# sch_v4_cdr.net
KiCad netlist of a schematic drawn in EAGLE
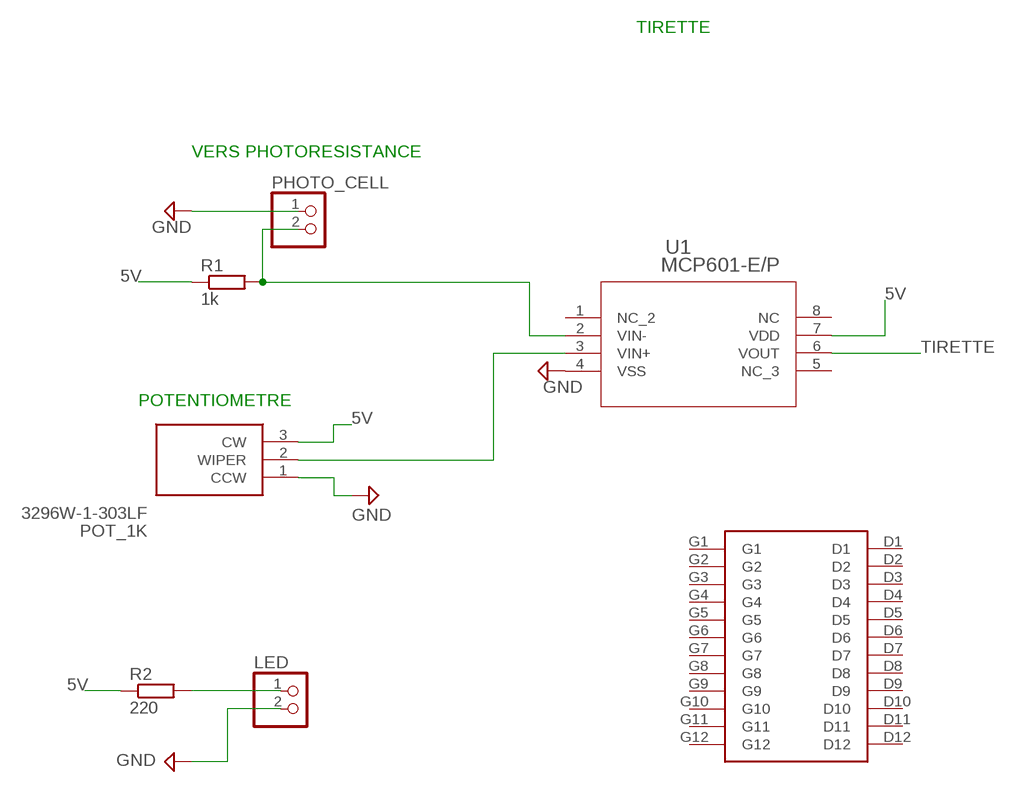
[diagram p0: schematic, sheet 1]
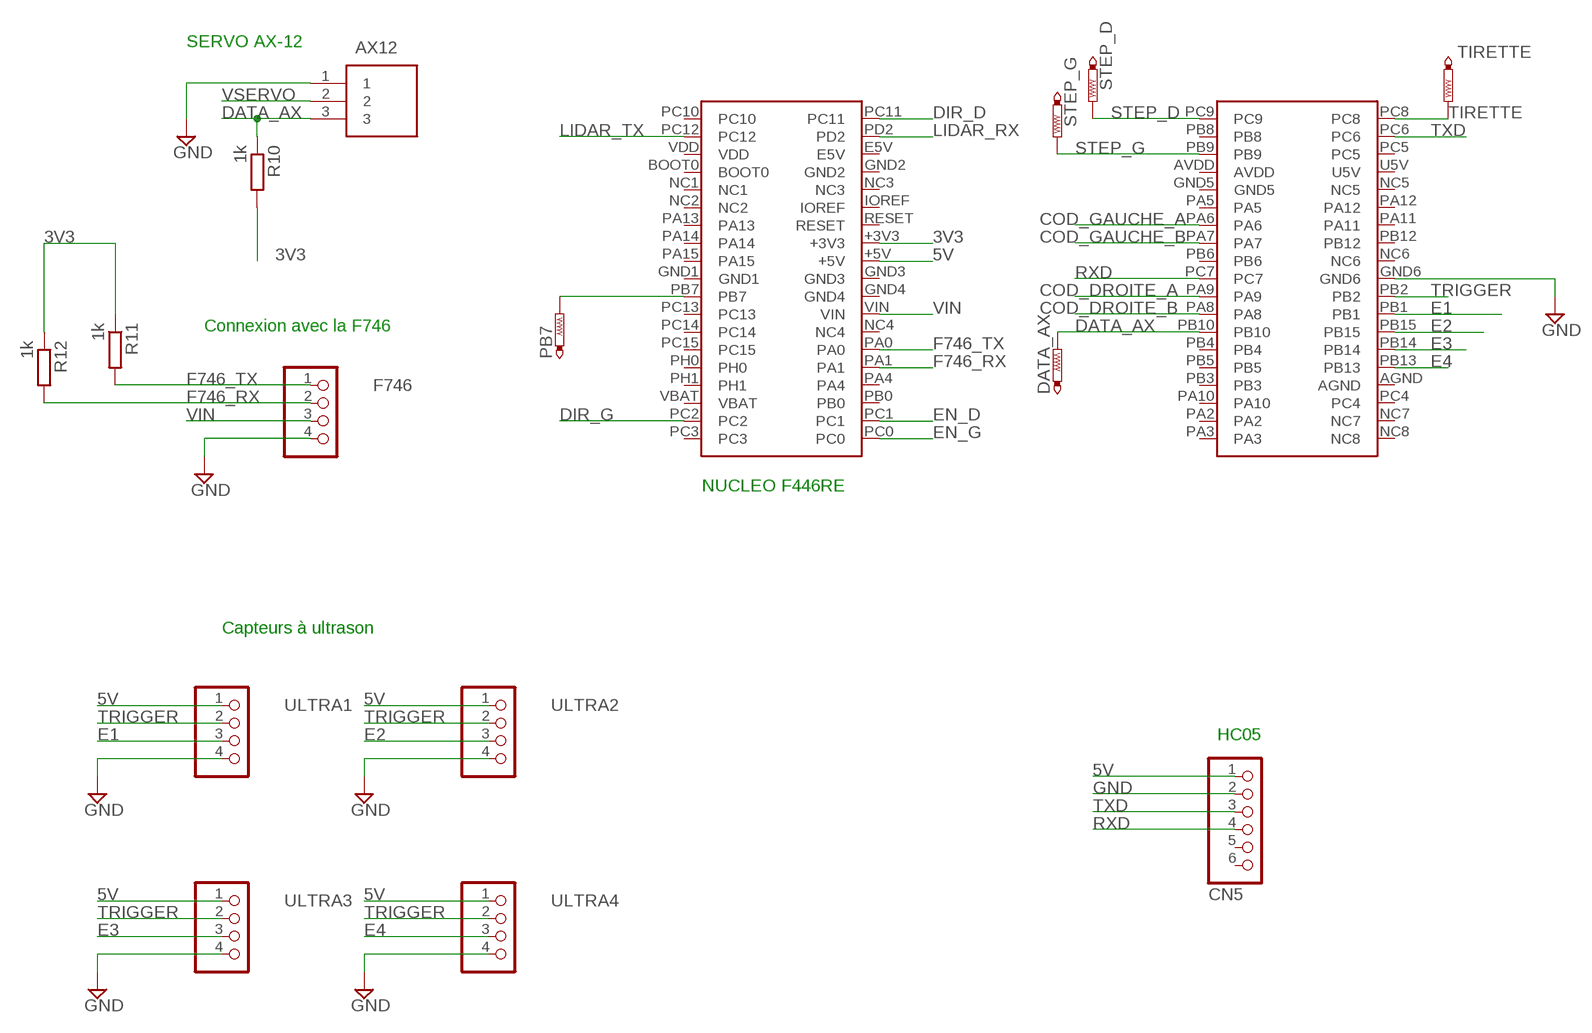
[diagram p1: schematic, sheet 2]
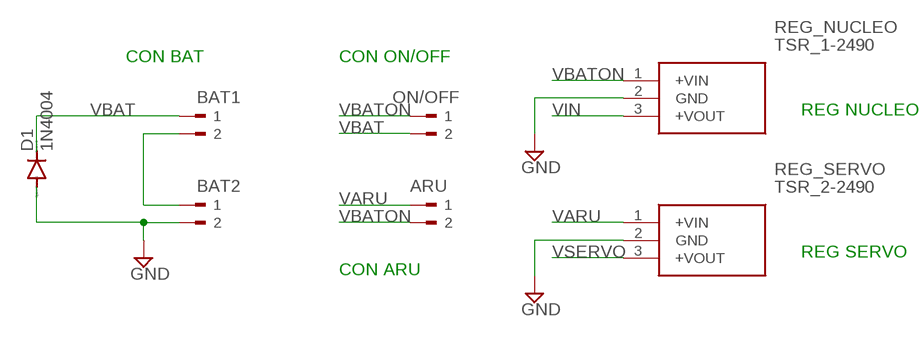
[diagram p2: schematic, sheet 3]
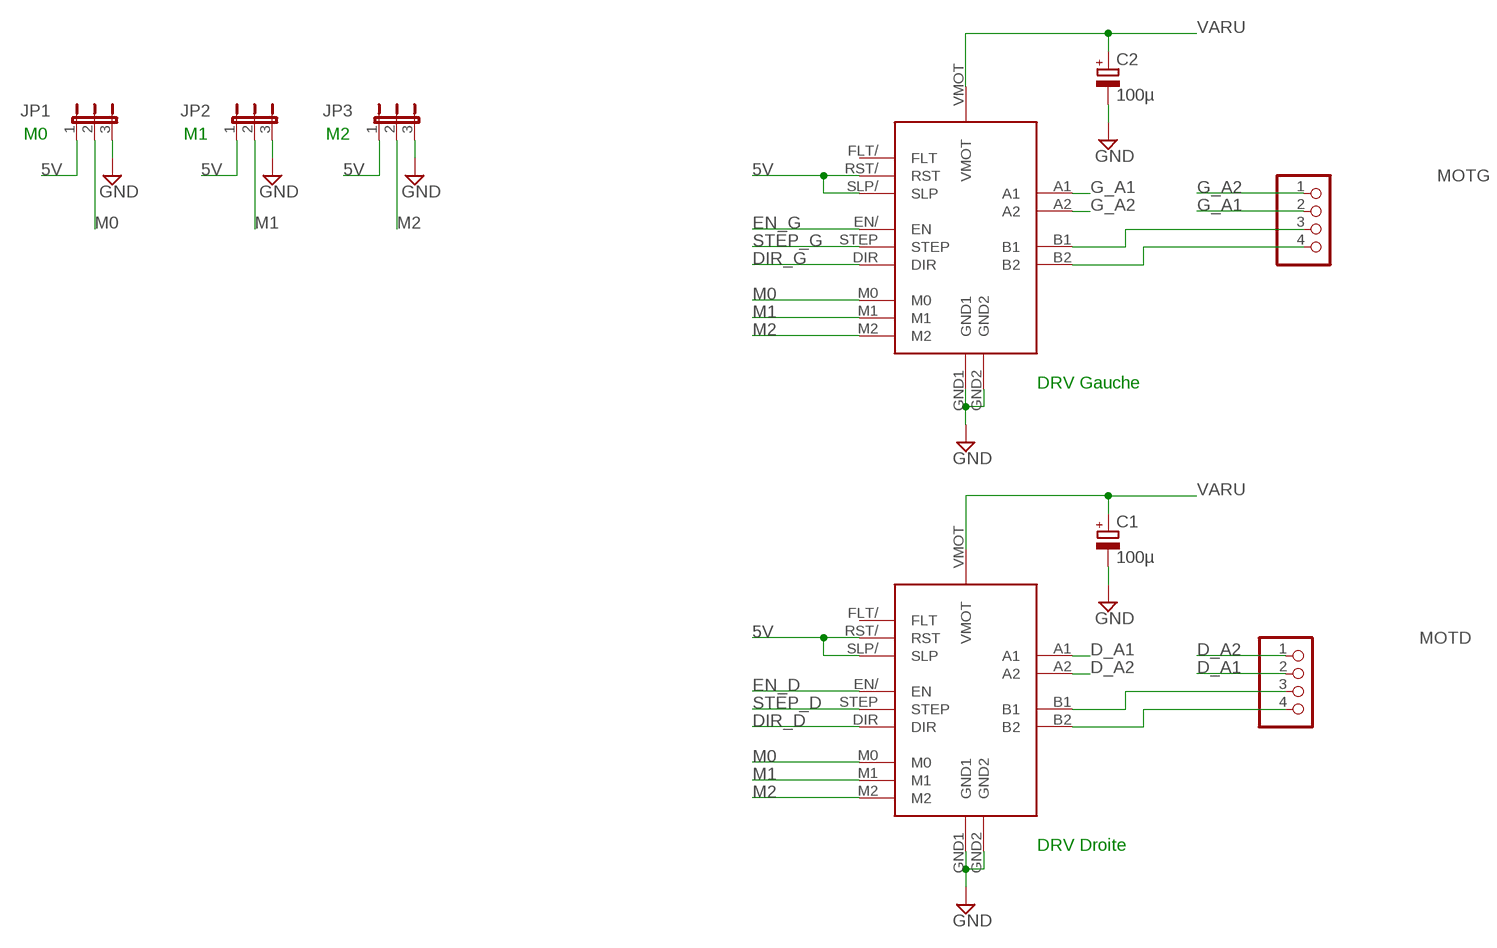
[diagram p3: schematic, sheet 4]
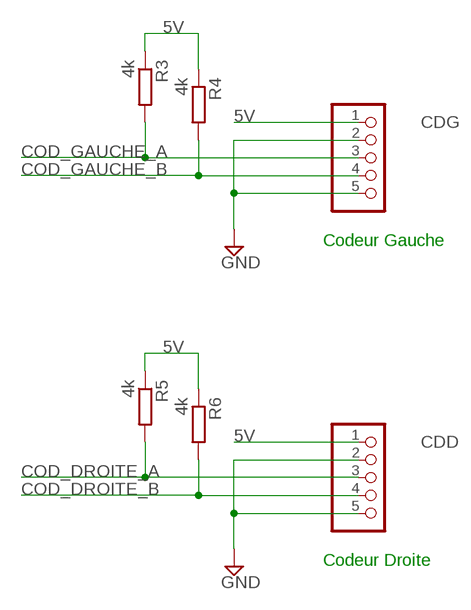
[diagram p4: schematic, sheet 5]
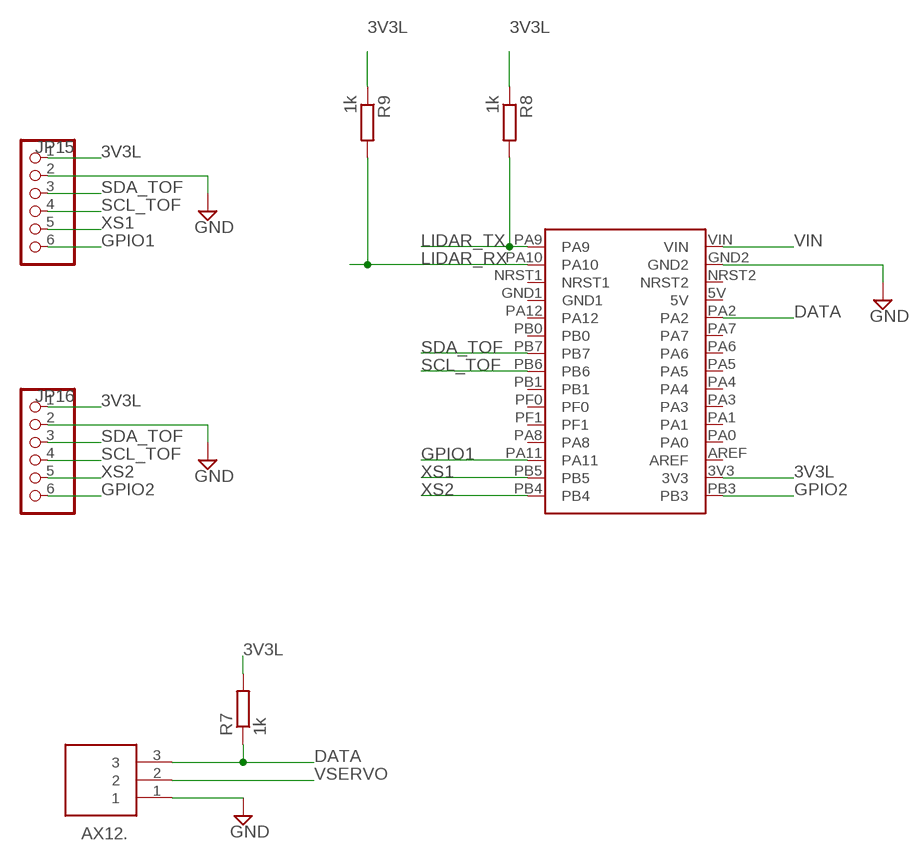
[diagram p5: schematic, sheet 6]

(export (version "E")
  (design (tool "Eeschema 10.0.6"))
  (components
    (comp (ref "AX12")
      (value "22-03-5035")
      (footprint "eagle-import:SHDR3W60P0X250_1X3_990X490X590")
      (fields (field (name "RS_PART_NUMBER") "6878048P"))
      (libsource (lib "eagle-import") (part "22-03-5035"))
    )
    (comp (ref "DATA_AX")
      (value "PTR1PAD1-13")
      (footprint "eagle-import:P1-13")
      (libsource (lib "eagle-import") (part "PTR1PAD1-13"))
    )
    (comp (ref "F746")
      (value "PINHD-1X4")
      (footprint "eagle-import:1X04")
      (libsource (lib "eagle-import") (part "PINHD-1X4"))
    )
    (comp (ref "JP4")
      (value "CN5")
      (footprint "eagle-import:1X06")
      (libsource (lib "eagle-import") (part "PINHD-1X6"))
    )
    (comp (ref "PB7")
      (value "PTR1PAD1-13")
      (footprint "eagle-import:P1-13")
      (libsource (lib "eagle-import") (part "PTR1PAD1-13"))
    )
    (comp (ref "R10")
      (value "1k")
      (footprint "eagle-import:0204_7")
      (libsource (lib "eagle-import") (part "R-EU_0204/7"))
    )
    (comp (ref "R11")
      (value "1k")
      (footprint "eagle-import:0204_7")
      (libsource (lib "eagle-import") (part "R-EU_0204/7"))
    )
    (comp (ref "R12")
      (value "1k")
      (footprint "eagle-import:0204_7")
      (libsource (lib "eagle-import") (part "R-EU_0204/7"))
    )
    (comp (ref "STEP_D")
      (value "PTR1PAD1-13")
      (footprint "eagle-import:P1-13")
      (libsource (lib "eagle-import") (part "PTR1PAD1-13"))
    )
    (comp (ref "STEP_G")
      (value "PTR1PAD1-13")
      (footprint "eagle-import:P1-13")
      (libsource (lib "eagle-import") (part "PTR1PAD1-13"))
    )
    (comp (ref "TIRETTE")
      (value "PTR1PAD1-13")
      (footprint "eagle-import:P1-13")
      (libsource (lib "eagle-import") (part "PTR1PAD1-13"))
    )
    (comp (ref "U$1")
      (value "NUCLEO_F446RE")
      (footprint "eagle-import:MB1136")
      (libsource (lib "eagle-import") (part "NUCLEO_F446RE"))
    )
    (comp (ref "ULTRA1")
      (value "PINHD-1X4")
      (footprint "eagle-import:1X04")
      (libsource (lib "eagle-import") (part "PINHD-1X4"))
    )
    (comp (ref "ULTRA2")
      (value "PINHD-1X4")
      (footprint "eagle-import:1X04")
      (libsource (lib "eagle-import") (part "PINHD-1X4"))
    )
    (comp (ref "ULTRA3")
      (value "PINHD-1X4")
      (footprint "eagle-import:1X04")
      (libsource (lib "eagle-import") (part "PINHD-1X4"))
    )
    (comp (ref "ULTRA4")
      (value "PINHD-1X4")
      (footprint "eagle-import:1X04")
      (libsource (lib "eagle-import") (part "PINHD-1X4"))
    )
    (comp (ref "CDD")
      (value "PINHD-1X5")
      (footprint "eagle-import:1X05")
      (libsource (lib "eagle-import") (part "PINHD-1X5"))
    )
    (comp (ref "CDG")
      (value "PINHD-1X5")
      (footprint "eagle-import:1X05")
      (libsource (lib "eagle-import") (part "PINHD-1X5"))
    )
    (comp (ref "R3")
      (value "4k")
      (footprint "eagle-import:0204_7")
      (libsource (lib "eagle-import") (part "R-EU_0204/7"))
    )
    (comp (ref "R4")
      (value "4k")
      (footprint "eagle-import:0204_7")
      (libsource (lib "eagle-import") (part "R-EU_0204/7"))
    )
    (comp (ref "R5")
      (value "4k")
      (footprint "eagle-import:0204_7")
      (libsource (lib "eagle-import") (part "R-EU_0204/7"))
    )
    (comp (ref "R6")
      (value "4k")
      (footprint "eagle-import:0204_7")
      (libsource (lib "eagle-import") (part "R-EU_0204/7"))
    )
    (comp (ref "C1")
      (value "100µ")
      (footprint "eagle-import:SANYO-OSCON_A")
      (libsource (lib "eagle-import") (part "CPOL-EUSANYO_A"))
    )
    (comp (ref "C2")
      (value "100µ")
      (footprint "eagle-import:SANYO-OSCON_A")
      (libsource (lib "eagle-import") (part "CPOL-EUSANYO_A"))
    )
    (comp (ref "JP1")
      (value "JP2E")
      (footprint "eagle-import:JP2")
      (libsource (lib "eagle-import") (part "JP2E"))
    )
    (comp (ref "JP2")
      (value "JP2E")
      (footprint "eagle-import:JP2")
      (libsource (lib "eagle-import") (part "JP2E"))
    )
    (comp (ref "JP3")
      (value "JP2E")
      (footprint "eagle-import:JP2")
      (libsource (lib "eagle-import") (part "JP2E"))
    )
    (comp (ref "MOTD")
      (value "PINHD-1X4")
      (footprint "eagle-import:1X04")
      (libsource (lib "eagle-import") (part "PINHD-1X4"))
    )
    (comp (ref "MOTG")
      (value "PINHD-1X4")
      (footprint "eagle-import:1X04")
      (libsource (lib "eagle-import") (part "PINHD-1X4"))
    )
    (comp (ref "U$2")
      (value "POLOLU_DRV8825")
      (footprint "eagle-import:POLOLU_DRV8825")
      (libsource (lib "eagle-import") (part "POLOLU_DRV8825"))
    )
    (comp (ref "U$3")
      (value "POLOLU_DRV8825")
      (footprint "eagle-import:POLOLU_DRV8825")
      (libsource (lib "eagle-import") (part "POLOLU_DRV8825"))
    )
    (comp (ref "ARU")
      (value "180G-2")
      (footprint "eagle-import:180G-2")
      (libsource (lib "eagle-import") (part "180G-2"))
    )
    (comp (ref "BAT1")
      (value "180G-2")
      (footprint "eagle-import:180G-2")
      (libsource (lib "eagle-import") (part "180G-2"))
    )
    (comp (ref "BAT2")
      (value "180G-2")
      (footprint "eagle-import:180G-2")
      (libsource (lib "eagle-import") (part "180G-2"))
    )
    (comp (ref "D1")
      (value "1N4004")
      (footprint "eagle-import:DO41-10")
      (libsource (lib "eagle-import") (part "1N4004"))
    )
    (comp (ref "ON/OFF")
      (value "180G-2")
      (footprint "eagle-import:180G-2")
      (libsource (lib "eagle-import") (part "180G-2"))
    )
    (comp (ref "REG_NUCLEO")
      (value "TSR_1-2490")
      (footprint "eagle-import:TSR_1-24XX")
      (libsource (lib "eagle-import") (part "TSR_1-2490"))
    )
    (comp (ref "REG_SERVO")
      (value "TSR_2-2490")
      (footprint "eagle-import:TSR_2-24XX")
      (fields
        (field (name "MANUFACTURER_PART_NUMBER") "TSR 2-2490")
        (field (name "MOUSER_PART_NUMBER") "495-TSR2-2490")
      )
      (libsource (lib "eagle-import") (part "TSR_2-2490"))
    )
    (comp (ref "LED")
      (value "PINHD-1X2")
      (footprint "eagle-import:1X02")
      (libsource (lib "eagle-import") (part "PINHD-1X2"))
    )
    (comp (ref "PHOTO_CELL")
      (value "PINHD-1X2")
      (footprint "eagle-import:1X02")
      (libsource (lib "eagle-import") (part "PINHD-1X2"))
    )
    (comp (ref "POT_1K")
      (value "3296W-1-303LF")
      (footprint "eagle-import:3296W-1")
      (fields (field (name "MOUSER_PART_NUMBER") "652-3296W-1-303LF"))
      (libsource (lib "eagle-import") (part "3296W-1-303LF"))
    )
    (comp (ref "R1")
      (value "1k")
      (footprint "eagle-import:0204_7")
      (libsource (lib "eagle-import") (part "R-EU_0204/7"))
    )
    (comp (ref "R2")
      (value "220")
      (footprint "eagle-import:0204_7")
      (libsource (lib "eagle-import") (part "R-EU_0204/7"))
    )
    (comp (ref "U$5")
      (value "MATRIX_12X12")
      (footprint "eagle-import:MATRIX_12X12")
      (libsource (lib "eagle-import") (part "MATRIX_12X12"))
    )
    (comp (ref "U1")
      (value "MCP601-E/P")
      (footprint "eagle-import:PDIP8_300MC_MCH")
      (fields (field (name "COPYRIGHT") "Copyright (C) 2018 Accelerated Designs. All rights reserved"))
      (libsource (lib "eagle-import") (part "MCP601-E/P"))
    )
    (comp (ref "AX12.")
      (value "22-03-5035")
      (footprint "eagle-import:SHDR3W60P0X250_1X3_990X490X590")
      (fields (field (name "RS_PART_NUMBER") "6878048P"))
      (libsource (lib "eagle-import") (part "22-03-5035"))
    )
    (comp (ref "JP15")
      (value "PINHD-1X6")
      (footprint "eagle-import:1X06")
      (libsource (lib "eagle-import") (part "PINHD-1X6"))
    )
    (comp (ref "JP16")
      (value "PINHD-1X6")
      (footprint "eagle-import:1X06")
      (libsource (lib "eagle-import") (part "PINHD-1X6"))
    )
    (comp (ref "R7")
      (value "1k")
      (footprint "eagle-import:0204_7")
      (libsource (lib "eagle-import") (part "R-EU_0204/7"))
    )
    (comp (ref "R8")
      (value "1k")
      (footprint "eagle-import:0204_7")
      (libsource (lib "eagle-import") (part "R-EU_0204/7"))
    )
    (comp (ref "R9")
      (value "1k")
      (footprint "eagle-import:0204_7")
      (libsource (lib "eagle-import") (part "R-EU_0204/7"))
    )
    (comp (ref "U$4")
      (value "NUCLEO_F303K8")
      (footprint "eagle-import:MB1180")
      (libsource (lib "eagle-import") (part "NUCLEO_F303K8"))
    )
  )
  (nets
    (net (code "1") (name "3V3") (class "Default")
      (node (ref "R10") (pin "2") (pinfunction "2_2") (pintype "passive"))
      (node (ref "R11") (pin "1") (pinfunction "1_1") (pintype "passive"))
      (node (ref "R12") (pin "1") (pinfunction "1_1") (pintype "passive"))
      (node (ref "U$1") (pin "+3V3") (pinfunction "+3V3_+3V3") (pintype "bidirectional"))
    )
    (net (code "2") (name "3V3L") (class "Default")
      (node (ref "JP15") (pin "1") (pinfunction "1_1") (pintype "passive"))
      (node (ref "JP16") (pin "1") (pinfunction "1_1") (pintype "passive"))
      (node (ref "R7") (pin "2") (pinfunction "2_2") (pintype "passive"))
      (node (ref "R8") (pin "1") (pinfunction "1_1") (pintype "passive"))
      (node (ref "R9") (pin "1") (pinfunction "1_1") (pintype "passive"))
      (node (ref "U$4") (pin "3V3") (pinfunction "3V3_3V3") (pintype "bidirectional"))
    )
    (net (code "3") (name "5V") (class "Default")
      (node (ref "CDD") (pin "1") (pinfunction "1_1") (pintype "passive"))
      (node (ref "CDG") (pin "1") (pinfunction "1_1") (pintype "passive"))
      (node (ref "JP1") (pin "1") (pinfunction "1_1") (pintype "passive"))
      (node (ref "JP2") (pin "1") (pinfunction "1_1") (pintype "passive"))
      (node (ref "JP3") (pin "1") (pinfunction "1_1") (pintype "passive"))
      (node (ref "JP4") (pin "1") (pinfunction "1_1") (pintype "passive"))
      (node (ref "POT_1K") (pin "3") (pinfunction "CW_3") (pintype "bidirectional"))
      (node (ref "R1") (pin "1") (pinfunction "1_1") (pintype "passive"))
      (node (ref "R2") (pin "1") (pinfunction "1_1") (pintype "passive"))
      (node (ref "R3") (pin "1") (pinfunction "1_1") (pintype "passive"))
      (node (ref "R4") (pin "1") (pinfunction "1_1") (pintype "passive"))
      (node (ref "R5") (pin "1") (pinfunction "1_1") (pintype "passive"))
      (node (ref "R6") (pin "1") (pinfunction "1_1") (pintype "passive"))
      (node (ref "U$1") (pin "+5V") (pinfunction "+5V_+5V") (pintype "bidirectional"))
      (node (ref "U$2") (pin "RST/") (pinfunction "RST_RST/") (pintype "bidirectional"))
      (node (ref "U$2") (pin "SLP/") (pinfunction "SLP_SLP/") (pintype "bidirectional"))
      (node (ref "U$3") (pin "RST/") (pinfunction "RST_RST/") (pintype "bidirectional"))
      (node (ref "U$3") (pin "SLP/") (pinfunction "SLP_SLP/") (pintype "bidirectional"))
      (node (ref "U1") (pin "7") (pinfunction "VDD_7") (pintype "passive"))
      (node (ref "ULTRA1") (pin "1") (pinfunction "1_1") (pintype "passive"))
      (node (ref "ULTRA2") (pin "1") (pinfunction "1_1") (pintype "passive"))
      (node (ref "ULTRA3") (pin "1") (pinfunction "1_1") (pintype "passive"))
      (node (ref "ULTRA4") (pin "1") (pinfunction "1_1") (pintype "passive"))
    )
    (net (code "4") (name "COD_DROITE_A") (class "Default")
      (node (ref "CDD") (pin "3") (pinfunction "3_3") (pintype "passive"))
      (node (ref "R5") (pin "2") (pinfunction "2_2") (pintype "passive"))
      (node (ref "U$1") (pin "PA9") (pinfunction "PA9_PA9") (pintype "bidirectional"))
    )
    (net (code "5") (name "COD_DROITE_B") (class "Default")
      (node (ref "CDD") (pin "4") (pinfunction "4_4") (pintype "passive"))
      (node (ref "R6") (pin "2") (pinfunction "2_2") (pintype "passive"))
      (node (ref "U$1") (pin "PA8") (pinfunction "PA8_PA8") (pintype "bidirectional"))
    )
    (net (code "6") (name "COD_GAUCHE_A") (class "Default")
      (node (ref "CDG") (pin "3") (pinfunction "3_3") (pintype "passive"))
      (node (ref "R3") (pin "2") (pinfunction "2_2") (pintype "passive"))
      (node (ref "U$1") (pin "PA6") (pinfunction "PA6_PA6") (pintype "bidirectional"))
    )
    (net (code "7") (name "COD_GAUCHE_B") (class "Default")
      (node (ref "CDG") (pin "4") (pinfunction "4_4") (pintype "passive"))
      (node (ref "R4") (pin "2") (pinfunction "2_2") (pintype "passive"))
      (node (ref "U$1") (pin "PA7") (pinfunction "PA7_PA7") (pintype "bidirectional"))
    )
    (net (code "8") (name "DATA") (class "Default")
      (node (ref "AX12.") (pin "3") (pinfunction "3_3") (pintype "bidirectional"))
      (node (ref "R7") (pin "1") (pinfunction "1_1") (pintype "passive"))
      (node (ref "U$4") (pin "PA2") (pinfunction "PA2_PA2") (pintype "bidirectional"))
    )
    (net (code "9") (name "DATA_AX") (class "Default")
      (node (ref "AX12") (pin "3") (pinfunction "3_3") (pintype "bidirectional"))
      (node (ref "DATA_AX") (pin "TP") (pinfunction "TP_TP") (pintype "input"))
      (node (ref "R10") (pin "1") (pinfunction "1_1") (pintype "passive"))
      (node (ref "U$1") (pin "PB10") (pinfunction "PB10_PB10") (pintype "bidirectional"))
    )
    (net (code "10") (name "DIR_D") (class "Default")
      (node (ref "U$1") (pin "PC11") (pinfunction "PC11_PC11") (pintype "bidirectional"))
      (node (ref "U$3") (pin "DIR") (pinfunction "DIR_DIR") (pintype "bidirectional"))
    )
    (net (code "11") (name "DIR_G") (class "Default")
      (node (ref "U$1") (pin "PC2") (pinfunction "PC2_PC2") (pintype "bidirectional"))
      (node (ref "U$2") (pin "DIR") (pinfunction "DIR_DIR") (pintype "bidirectional"))
    )
    (net (code "12") (name "D_A1") (class "Default")
      (node (ref "MOTD") (pin "2") (pinfunction "2_2") (pintype "passive"))
      (node (ref "U$3") (pin "A1") (pinfunction "A1_A1") (pintype "bidirectional"))
    )
    (net (code "13") (name "D_A2") (class "Default")
      (node (ref "MOTD") (pin "1") (pinfunction "1_1") (pintype "passive"))
      (node (ref "U$3") (pin "A2") (pinfunction "A2_A2") (pintype "bidirectional"))
    )
    (net (code "14") (name "E1") (class "Default")
      (node (ref "U$1") (pin "PB1") (pinfunction "PB1_PB1") (pintype "bidirectional"))
      (node (ref "ULTRA1") (pin "3") (pinfunction "3_3") (pintype "passive"))
    )
    (net (code "15") (name "E2") (class "Default")
      (node (ref "U$1") (pin "PB15") (pinfunction "PB15_PB15") (pintype "bidirectional"))
      (node (ref "ULTRA2") (pin "3") (pinfunction "3_3") (pintype "passive"))
    )
    (net (code "16") (name "E3") (class "Default")
      (node (ref "U$1") (pin "PB14") (pinfunction "PB14_PB14") (pintype "bidirectional"))
      (node (ref "ULTRA3") (pin "3") (pinfunction "3_3") (pintype "passive"))
    )
    (net (code "17") (name "E4") (class "Default")
      (node (ref "U$1") (pin "PB13") (pinfunction "PB13_PB13") (pintype "bidirectional"))
      (node (ref "ULTRA4") (pin "3") (pinfunction "3_3") (pintype "passive"))
    )
    (net (code "18") (name "EN_D") (class "Default")
      (node (ref "U$1") (pin "PC1") (pinfunction "PC1_PC1") (pintype "bidirectional"))
      (node (ref "U$3") (pin "EN/") (pinfunction "EN_EN/") (pintype "bidirectional"))
    )
    (net (code "19") (name "EN_G") (class "Default")
      (node (ref "U$1") (pin "PC0") (pinfunction "PC0_PC0") (pintype "bidirectional"))
      (node (ref "U$2") (pin "EN/") (pinfunction "EN_EN/") (pintype "bidirectional"))
    )
    (net (code "20") (name "F746_RX") (class "Default")
      (node (ref "F746") (pin "2") (pinfunction "2_2") (pintype "passive"))
      (node (ref "R12") (pin "2") (pinfunction "2_2") (pintype "passive"))
      (node (ref "U$1") (pin "PA1") (pinfunction "PA1_PA1") (pintype "bidirectional"))
    )
    (net (code "21") (name "F746_TX") (class "Default")
      (node (ref "F746") (pin "1") (pinfunction "1_1") (pintype "passive"))
      (node (ref "R11") (pin "2") (pinfunction "2_2") (pintype "passive"))
      (node (ref "U$1") (pin "PA0") (pinfunction "PA0_PA0") (pintype "bidirectional"))
    )
    (net (code "22") (name "GND") (class "Default")
      (node (ref "AX12") (pin "1") (pinfunction "1_1") (pintype "bidirectional"))
      (node (ref "AX12.") (pin "1") (pinfunction "1_1") (pintype "bidirectional"))
      (node (ref "BAT2") (pin "2") (pinfunction "2_2") (pintype "passive"))
      (node (ref "C1") (pin "-") (pinfunction "-_-") (pintype "passive"))
      (node (ref "C2") (pin "-") (pinfunction "-_-") (pintype "passive"))
      (node (ref "CDD") (pin "2") (pinfunction "2_2") (pintype "passive"))
      (node (ref "CDD") (pin "5") (pinfunction "5_5") (pintype "passive"))
      (node (ref "CDG") (pin "2") (pinfunction "2_2") (pintype "passive"))
      (node (ref "CDG") (pin "5") (pinfunction "5_5") (pintype "passive"))
      (node (ref "D1") (pin "A") (pinfunction "A_A") (pintype "passive"))
      (node (ref "F746") (pin "4") (pinfunction "4_4") (pintype "passive"))
      (node (ref "JP1") (pin "3") (pinfunction "3_3") (pintype "passive"))
      (node (ref "JP15") (pin "2") (pinfunction "2_2") (pintype "passive"))
      (node (ref "JP16") (pin "2") (pinfunction "2_2") (pintype "passive"))
      (node (ref "JP2") (pin "3") (pinfunction "3_3") (pintype "passive"))
      (node (ref "JP3") (pin "3") (pinfunction "3_3") (pintype "passive"))
      (node (ref "JP4") (pin "2") (pinfunction "2_2") (pintype "passive"))
      (node (ref "LED") (pin "2") (pinfunction "2_2") (pintype "passive"))
      (node (ref "PHOTO_CELL") (pin "1") (pinfunction "1_1") (pintype "passive"))
      (node (ref "POT_1K") (pin "1") (pinfunction "CCW_1") (pintype "bidirectional"))
      (node (ref "REG_NUCLEO") (pin "2") (pinfunction "GND_2") (pintype "bidirectional"))
      (node (ref "REG_SERVO") (pin "2") (pinfunction "GND_2") (pintype "bidirectional"))
      (node (ref "U$1") (pin "GND6") (pinfunction "GND6_GND6") (pintype "bidirectional"))
      (node (ref "U$2") (pin "GND1") (pinfunction "GND1_GND1") (pintype "bidirectional"))
      (node (ref "U$2") (pin "GND2") (pinfunction "GND2_GND2") (pintype "bidirectional"))
      (node (ref "U$3") (pin "GND1") (pinfunction "GND1_GND1") (pintype "bidirectional"))
      (node (ref "U$3") (pin "GND2") (pinfunction "GND2_GND2") (pintype "bidirectional"))
      (node (ref "U$4") (pin "GND2") (pinfunction "GND2_GND2") (pintype "bidirectional"))
      (node (ref "U1") (pin "4") (pinfunction "VSS_4") (pintype "passive"))
      (node (ref "ULTRA1") (pin "4") (pinfunction "4_4") (pintype "passive"))
      (node (ref "ULTRA2") (pin "4") (pinfunction "4_4") (pintype "passive"))
      (node (ref "ULTRA3") (pin "4") (pinfunction "4_4") (pintype "passive"))
      (node (ref "ULTRA4") (pin "4") (pinfunction "4_4") (pintype "passive"))
    )
    (net (code "23") (name "GPIO1") (class "Default")
      (node (ref "JP15") (pin "6") (pinfunction "6_6") (pintype "passive"))
      (node (ref "U$4") (pin "PA11") (pinfunction "PA11_PA11") (pintype "bidirectional"))
    )
    (net (code "24") (name "GPIO2") (class "Default")
      (node (ref "JP16") (pin "6") (pinfunction "6_6") (pintype "passive"))
      (node (ref "U$4") (pin "PB3") (pinfunction "PB3_PB3") (pintype "bidirectional"))
    )
    (net (code "25") (name "G_A1") (class "Default")
      (node (ref "MOTG") (pin "2") (pinfunction "2_2") (pintype "passive"))
      (node (ref "U$2") (pin "A1") (pinfunction "A1_A1") (pintype "bidirectional"))
    )
    (net (code "26") (name "G_A2") (class "Default")
      (node (ref "MOTG") (pin "1") (pinfunction "1_1") (pintype "passive"))
      (node (ref "U$2") (pin "A2") (pinfunction "A2_A2") (pintype "bidirectional"))
    )
    (net (code "27") (name "LIDAR_RX") (class "Default")
      (node (ref "R9") (pin "2") (pinfunction "2_2") (pintype "passive"))
      (node (ref "U$1") (pin "PD2") (pinfunction "PD2_PD2") (pintype "bidirectional"))
      (node (ref "U$4") (pin "PA10") (pinfunction "PA10_PA10") (pintype "bidirectional"))
    )
    (net (code "28") (name "LIDAR_TX") (class "Default")
      (node (ref "R8") (pin "2") (pinfunction "2_2") (pintype "passive"))
      (node (ref "U$1") (pin "PC12") (pinfunction "PC12_PC12") (pintype "bidirectional"))
      (node (ref "U$4") (pin "PA9") (pinfunction "PA9_PA9") (pintype "bidirectional"))
    )
    (net (code "29") (name "M0") (class "Default")
      (node (ref "JP1") (pin "2") (pinfunction "2_2") (pintype "passive"))
      (node (ref "U$2") (pin "M0") (pinfunction "M0_M0") (pintype "bidirectional"))
      (node (ref "U$3") (pin "M0") (pinfunction "M0_M0") (pintype "bidirectional"))
    )
    (net (code "30") (name "M1") (class "Default")
      (node (ref "JP2") (pin "2") (pinfunction "2_2") (pintype "passive"))
      (node (ref "U$2") (pin "M1") (pinfunction "M1_M1") (pintype "bidirectional"))
      (node (ref "U$3") (pin "M1") (pinfunction "M1_M1") (pintype "bidirectional"))
    )
    (net (code "31") (name "M2") (class "Default")
      (node (ref "JP3") (pin "2") (pinfunction "2_2") (pintype "passive"))
      (node (ref "U$2") (pin "M2") (pinfunction "M2_M2") (pintype "bidirectional"))
      (node (ref "U$3") (pin "M2") (pinfunction "M2_M2") (pintype "bidirectional"))
    )
    (net (code "32") (name "Net-(BAT1-Pad2)") (class "Default")
      (node (ref "BAT1") (pin "2") (pinfunction "2_2") (pintype "passive"))
      (node (ref "BAT2") (pin "1") (pinfunction "1_1") (pintype "passive"))
    )
    (net (code "33") (name "Net-(LED-Pad1)") (class "Default")
      (node (ref "LED") (pin "1") (pinfunction "1_1") (pintype "passive"))
      (node (ref "R2") (pin "2") (pinfunction "2_2") (pintype "passive"))
    )
    (net (code "34") (name "Net-(MOTD-Pad3)") (class "Default")
      (node (ref "MOTD") (pin "3") (pinfunction "3_3") (pintype "passive"))
      (node (ref "U$3") (pin "B1") (pinfunction "B1_B1") (pintype "bidirectional"))
    )
    (net (code "35") (name "Net-(MOTD-Pad4)") (class "Default")
      (node (ref "MOTD") (pin "4") (pinfunction "4_4") (pintype "passive"))
      (node (ref "U$3") (pin "B2") (pinfunction "B2_B2") (pintype "bidirectional"))
    )
    (net (code "36") (name "Net-(MOTG-Pad3)") (class "Default")
      (node (ref "MOTG") (pin "3") (pinfunction "3_3") (pintype "passive"))
      (node (ref "U$2") (pin "B1") (pinfunction "B1_B1") (pintype "bidirectional"))
    )
    (net (code "37") (name "Net-(MOTG-Pad4)") (class "Default")
      (node (ref "MOTG") (pin "4") (pinfunction "4_4") (pintype "passive"))
      (node (ref "U$2") (pin "B2") (pinfunction "B2_B2") (pintype "bidirectional"))
    )
    (net (code "38") (name "Net-(PB7-PadTP)") (class "Default")
      (node (ref "PB7") (pin "TP") (pinfunction "TP_TP") (pintype "input"))
      (node (ref "U$1") (pin "PB7") (pinfunction "PB7_PB7") (pintype "bidirectional"))
    )
    (net (code "39") (name "Net-(POT_1K-WIPER)") (class "Default")
      (node (ref "POT_1K") (pin "2") (pinfunction "WIPER_2") (pintype "bidirectional"))
      (node (ref "U1") (pin "3") (pinfunction "VIN+_3") (pintype "passive"))
    )
    (net (code "40") (name "Net-(U1-VIN-)") (class "Default")
      (node (ref "PHOTO_CELL") (pin "2") (pinfunction "2_2") (pintype "passive"))
      (node (ref "R1") (pin "2") (pinfunction "2_2") (pintype "passive"))
      (node (ref "U1") (pin "2") (pinfunction "VIN-_2") (pintype "passive"))
    )
    (net (code "41") (name "RXD") (class "Default")
      (node (ref "JP4") (pin "4") (pinfunction "4_4") (pintype "passive"))
      (node (ref "U$1") (pin "PC7") (pinfunction "PC7_PC7") (pintype "bidirectional"))
    )
    (net (code "42") (name "SCL_TOF") (class "Default")
      (node (ref "JP15") (pin "4") (pinfunction "4_4") (pintype "passive"))
      (node (ref "JP16") (pin "4") (pinfunction "4_4") (pintype "passive"))
      (node (ref "U$4") (pin "PB6") (pinfunction "PB6_PB6") (pintype "bidirectional"))
    )
    (net (code "43") (name "SDA_TOF") (class "Default")
      (node (ref "JP15") (pin "3") (pinfunction "3_3") (pintype "passive"))
      (node (ref "JP16") (pin "3") (pinfunction "3_3") (pintype "passive"))
      (node (ref "U$4") (pin "PB7") (pinfunction "PB7_PB7") (pintype "bidirectional"))
    )
    (net (code "44") (name "STEP_D") (class "Default")
      (node (ref "STEP_D") (pin "TP") (pinfunction "TP_TP") (pintype "input"))
      (node (ref "U$1") (pin "PC9") (pinfunction "PC9_PC9") (pintype "bidirectional"))
      (node (ref "U$3") (pin "STEP") (pinfunction "STEP_STEP") (pintype "bidirectional"))
    )
    (net (code "45") (name "STEP_G") (class "Default")
      (node (ref "STEP_G") (pin "TP") (pinfunction "TP_TP") (pintype "input"))
      (node (ref "U$1") (pin "PB9") (pinfunction "PB9_PB9") (pintype "bidirectional"))
      (node (ref "U$2") (pin "STEP") (pinfunction "STEP_STEP") (pintype "bidirectional"))
    )
    (net (code "46") (name "TIRETTE") (class "Default")
      (node (ref "TIRETTE") (pin "TP") (pinfunction "TP_TP") (pintype "input"))
      (node (ref "U$1") (pin "PC8") (pinfunction "PC8_PC8") (pintype "bidirectional"))
      (node (ref "U1") (pin "6") (pinfunction "VOUT_6") (pintype "passive"))
    )
    (net (code "47") (name "TRIGGER") (class "Default")
      (node (ref "U$1") (pin "PB2") (pinfunction "PB2_PB2") (pintype "bidirectional"))
      (node (ref "ULTRA1") (pin "2") (pinfunction "2_2") (pintype "passive"))
      (node (ref "ULTRA2") (pin "2") (pinfunction "2_2") (pintype "passive"))
      (node (ref "ULTRA3") (pin "2") (pinfunction "2_2") (pintype "passive"))
      (node (ref "ULTRA4") (pin "2") (pinfunction "2_2") (pintype "passive"))
    )
    (net (code "48") (name "TXD") (class "Default")
      (node (ref "JP4") (pin "3") (pinfunction "3_3") (pintype "passive"))
      (node (ref "U$1") (pin "PC6") (pinfunction "PC6_PC6") (pintype "bidirectional"))
    )
    (net (code "49") (name "VARU") (class "Default")
      (node (ref "ARU") (pin "1") (pinfunction "1_1") (pintype "passive"))
      (node (ref "C1") (pin "+") (pinfunction "+_+") (pintype "passive"))
      (node (ref "C2") (pin "+") (pinfunction "+_+") (pintype "passive"))
      (node (ref "REG_SERVO") (pin "1") (pinfunction "+VIN_1") (pintype "bidirectional"))
      (node (ref "U$2") (pin "VMOT") (pinfunction "VMOT_VMOT") (pintype "bidirectional"))
      (node (ref "U$3") (pin "VMOT") (pinfunction "VMOT_VMOT") (pintype "bidirectional"))
    )
    (net (code "50") (name "VBAT") (class "Default")
      (node (ref "BAT1") (pin "1") (pinfunction "1_1") (pintype "passive"))
      (node (ref "D1") (pin "C") (pinfunction "C_C") (pintype "passive"))
      (node (ref "ON/OFF") (pin "2") (pinfunction "2_2") (pintype "passive"))
    )
    (net (code "51") (name "VBATON") (class "Default")
      (node (ref "ARU") (pin "2") (pinfunction "2_2") (pintype "passive"))
      (node (ref "ON/OFF") (pin "1") (pinfunction "1_1") (pintype "passive"))
      (node (ref "REG_NUCLEO") (pin "1") (pinfunction "+VIN_1") (pintype "bidirectional"))
    )
    (net (code "52") (name "VIN") (class "Default")
      (node (ref "F746") (pin "3") (pinfunction "3_3") (pintype "passive"))
      (node (ref "REG_NUCLEO") (pin "3") (pinfunction "+VOUT_3") (pintype "bidirectional"))
      (node (ref "U$1") (pin "VIN") (pinfunction "VIN_VIN") (pintype "bidirectional"))
      (node (ref "U$4") (pin "VIN") (pinfunction "VIN_VIN") (pintype "bidirectional"))
    )
    (net (code "53") (name "VSERVO") (class "Default")
      (node (ref "AX12") (pin "2") (pinfunction "2_2") (pintype "bidirectional"))
      (node (ref "AX12.") (pin "2") (pinfunction "2_2") (pintype "bidirectional"))
      (node (ref "REG_SERVO") (pin "3") (pinfunction "+VOUT_3") (pintype "bidirectional"))
    )
    (net (code "54") (name "XS1") (class "Default")
      (node (ref "JP15") (pin "5") (pinfunction "5_5") (pintype "passive"))
      (node (ref "U$4") (pin "PB5") (pinfunction "PB5_PB5") (pintype "bidirectional"))
    )
    (net (code "55") (name "XS2") (class "Default")
      (node (ref "JP16") (pin "5") (pinfunction "5_5") (pintype "passive"))
      (node (ref "U$4") (pin "PB4") (pinfunction "PB4_PB4") (pintype "bidirectional"))
    )
    (net (code "56") (name "unconnected-(JP4-Pad5)") (class "Default")
      (node (ref "JP4") (pin "5") (pinfunction "5_5") (pintype "passive"))
    )
    (net (code "57") (name "unconnected-(JP4-Pad6)") (class "Default")
      (node (ref "JP4") (pin "6") (pinfunction "6_6") (pintype "passive"))
    )
    (net (code "58") (name "unconnected-(U$1-PadAGND)") (class "Default")
      (node (ref "U$1") (pin "AGND") (pinfunction "AGND_AGND") (pintype "bidirectional"))
    )
    (net (code "59") (name "unconnected-(U$1-PadAVDD)") (class "Default")
      (node (ref "U$1") (pin "AVDD") (pinfunction "AVDD_AVDD") (pintype "bidirectional"))
    )
    (net (code "60") (name "unconnected-(U$1-PadBOOT0)") (class "Default")
      (node (ref "U$1") (pin "BOOT0") (pinfunction "BOOT0_BOOT0") (pintype "bidirectional"))
    )
    (net (code "61") (name "unconnected-(U$1-PadE5V)") (class "Default")
      (node (ref "U$1") (pin "E5V") (pinfunction "E5V_E5V") (pintype "bidirectional"))
    )
    (net (code "62") (name "unconnected-(U$1-PadGND1)") (class "Default")
      (node (ref "U$1") (pin "GND1") (pinfunction "GND1_GND1") (pintype "bidirectional"))
    )
    (net (code "63") (name "unconnected-(U$1-PadGND2)") (class "Default")
      (node (ref "U$1") (pin "GND2") (pinfunction "GND2_GND2") (pintype "bidirectional"))
    )
    (net (code "64") (name "unconnected-(U$1-PadGND3)") (class "Default")
      (node (ref "U$1") (pin "GND3") (pinfunction "GND3_GND3") (pintype "bidirectional"))
    )
    (net (code "65") (name "unconnected-(U$1-PadGND4)") (class "Default")
      (node (ref "U$1") (pin "GND4") (pinfunction "GND4_GND4") (pintype "bidirectional"))
    )
    (net (code "66") (name "unconnected-(U$1-PadGND5)") (class "Default")
      (node (ref "U$1") (pin "GND5") (pinfunction "GND5_GND5") (pintype "bidirectional"))
    )
    (net (code "67") (name "unconnected-(U$1-PadIOREF)") (class "Default")
      (node (ref "U$1") (pin "IOREF") (pinfunction "IOREF_IOREF") (pintype "bidirectional"))
    )
    (net (code "68") (name "unconnected-(U$1-PadNC1)") (class "Default")
      (node (ref "U$1") (pin "NC1") (pinfunction "NC1_NC1") (pintype "no_connect"))
    )
    (net (code "69") (name "unconnected-(U$1-PadNC2)") (class "Default")
      (node (ref "U$1") (pin "NC2") (pinfunction "NC2_NC2") (pintype "no_connect"))
    )
    (net (code "70") (name "unconnected-(U$1-PadNC3)") (class "Default")
      (node (ref "U$1") (pin "NC3") (pinfunction "NC3_NC3") (pintype "no_connect"))
    )
    (net (code "71") (name "unconnected-(U$1-PadNC4)") (class "Default")
      (node (ref "U$1") (pin "NC4") (pinfunction "NC4_NC4") (pintype "no_connect"))
    )
    (net (code "72") (name "unconnected-(U$1-PadNC5)") (class "Default")
      (node (ref "U$1") (pin "NC5") (pinfunction "NC5_NC5") (pintype "no_connect"))
    )
    (net (code "73") (name "unconnected-(U$1-PadNC6)") (class "Default")
      (node (ref "U$1") (pin "NC6") (pinfunction "NC6_NC6") (pintype "no_connect"))
    )
    (net (code "74") (name "unconnected-(U$1-PadNC7)") (class "Default")
      (node (ref "U$1") (pin "NC7") (pinfunction "NC7_NC7") (pintype "no_connect"))
    )
    (net (code "75") (name "unconnected-(U$1-PadNC8)") (class "Default")
      (node (ref "U$1") (pin "NC8") (pinfunction "NC8_NC8") (pintype "no_connect"))
    )
    (net (code "76") (name "unconnected-(U$1-PadPA2)") (class "Default")
      (node (ref "U$1") (pin "PA2") (pinfunction "PA2_PA2") (pintype "bidirectional"))
    )
    (net (code "77") (name "unconnected-(U$1-PadPA3)") (class "Default")
      (node (ref "U$1") (pin "PA3") (pinfunction "PA3_PA3") (pintype "bidirectional"))
    )
    (net (code "78") (name "unconnected-(U$1-PadPA4)") (class "Default")
      (node (ref "U$1") (pin "PA4") (pinfunction "PA4_PA4") (pintype "bidirectional"))
    )
    (net (code "79") (name "unconnected-(U$1-PadPA5)") (class "Default")
      (node (ref "U$1") (pin "PA5") (pinfunction "PA5_PA5") (pintype "bidirectional"))
    )
    (net (code "80") (name "unconnected-(U$1-PadPA10)") (class "Default")
      (node (ref "U$1") (pin "PA10") (pinfunction "PA10_PA10") (pintype "bidirectional"))
    )
    (net (code "81") (name "unconnected-(U$1-PadPA11)") (class "Default")
      (node (ref "U$1") (pin "PA11") (pinfunction "PA11_PA11") (pintype "bidirectional"))
    )
    (net (code "82") (name "unconnected-(U$1-PadPA12)") (class "Default")
      (node (ref "U$1") (pin "PA12") (pinfunction "PA12_PA12") (pintype "bidirectional"))
    )
    (net (code "83") (name "unconnected-(U$1-PadPA13)") (class "Default")
      (node (ref "U$1") (pin "PA13") (pinfunction "PA13_PA13") (pintype "bidirectional"))
    )
    (net (code "84") (name "unconnected-(U$1-PadPA14)") (class "Default")
      (node (ref "U$1") (pin "PA14") (pinfunction "PA14_PA14") (pintype "bidirectional"))
    )
    (net (code "85") (name "unconnected-(U$1-PadPA15)") (class "Default")
      (node (ref "U$1") (pin "PA15") (pinfunction "PA15_PA15") (pintype "bidirectional"))
    )
    (net (code "86") (name "unconnected-(U$1-PadPB0)") (class "Default")
      (node (ref "U$1") (pin "PB0") (pinfunction "PB0_PB0") (pintype "bidirectional"))
    )
    (net (code "87") (name "unconnected-(U$1-PadPB3)") (class "Default")
      (node (ref "U$1") (pin "PB3") (pinfunction "PB3_PB3") (pintype "bidirectional"))
    )
    (net (code "88") (name "unconnected-(U$1-PadPB4)") (class "Default")
      (node (ref "U$1") (pin "PB4") (pinfunction "PB4_PB4") (pintype "bidirectional"))
    )
    (net (code "89") (name "unconnected-(U$1-PadPB5)") (class "Default")
      (node (ref "U$1") (pin "PB5") (pinfunction "PB5_PB5") (pintype "bidirectional"))
    )
    (net (code "90") (name "unconnected-(U$1-PadPB6)") (class "Default")
      (node (ref "U$1") (pin "PB6") (pinfunction "PB6_PB6") (pintype "bidirectional"))
    )
    (net (code "91") (name "unconnected-(U$1-PadPB8)") (class "Default")
      (node (ref "U$1") (pin "PB8") (pinfunction "PB8_PB8") (pintype "bidirectional"))
    )
    (net (code "92") (name "unconnected-(U$1-PadPB12)") (class "Default")
      (node (ref "U$1") (pin "PB12") (pinfunction "PB12_PB12") (pintype "bidirectional"))
    )
    (net (code "93") (name "unconnected-(U$1-PadPC3)") (class "Default")
      (node (ref "U$1") (pin "PC3") (pinfunction "PC3_PC3") (pintype "bidirectional"))
    )
    (net (code "94") (name "unconnected-(U$1-PadPC4)") (class "Default")
      (node (ref "U$1") (pin "PC4") (pinfunction "PC4_PC4") (pintype "bidirectional"))
    )
    (net (code "95") (name "unconnected-(U$1-PadPC5)") (class "Default")
      (node (ref "U$1") (pin "PC5") (pinfunction "PC5_PC5") (pintype "bidirectional"))
    )
    (net (code "96") (name "unconnected-(U$1-PadPC10)") (class "Default")
      (node (ref "U$1") (pin "PC10") (pinfunction "PC10_PC10") (pintype "bidirectional"))
    )
    (net (code "97") (name "unconnected-(U$1-PadPC13)") (class "Default")
      (node (ref "U$1") (pin "PC13") (pinfunction "PC13_PC13") (pintype "bidirectional"))
    )
    (net (code "98") (name "unconnected-(U$1-PadPC14)") (class "Default")
      (node (ref "U$1") (pin "PC14") (pinfunction "PC14_PC14") (pintype "bidirectional"))
    )
    (net (code "99") (name "unconnected-(U$1-PadPC15)") (class "Default")
      (node (ref "U$1") (pin "PC15") (pinfunction "PC15_PC15") (pintype "bidirectional"))
    )
    (net (code "100") (name "unconnected-(U$1-PadPH0)") (class "Default")
      (node (ref "U$1") (pin "PH0") (pinfunction "PH0_PH0") (pintype "bidirectional"))
    )
    (net (code "101") (name "unconnected-(U$1-PadPH1)") (class "Default")
      (node (ref "U$1") (pin "PH1") (pinfunction "PH1_PH1") (pintype "bidirectional"))
    )
    (net (code "102") (name "unconnected-(U$1-PadRESET)") (class "Default")
      (node (ref "U$1") (pin "RESET") (pinfunction "RESET_RESET") (pintype "bidirectional"))
    )
    (net (code "103") (name "unconnected-(U$1-PadU5V)") (class "Default")
      (node (ref "U$1") (pin "U5V") (pinfunction "U5V_U5V") (pintype "bidirectional"))
    )
    (net (code "104") (name "unconnected-(U$1-PadVBAT)") (class "Default")
      (node (ref "U$1") (pin "VBAT") (pinfunction "VBAT_VBAT") (pintype "bidirectional"))
    )
    (net (code "105") (name "unconnected-(U$1-PadVDD)") (class "Default")
      (node (ref "U$1") (pin "VDD") (pinfunction "VDD_VDD") (pintype "bidirectional"))
    )
    (net (code "106") (name "unconnected-(U$2-FLT-PadFLT{slash})") (class "Default")
      (node (ref "U$2") (pin "FLT/") (pinfunction "FLT_FLT/") (pintype "bidirectional"))
    )
    (net (code "107") (name "unconnected-(U$3-FLT-PadFLT{slash})") (class "Default")
      (node (ref "U$3") (pin "FLT/") (pinfunction "FLT_FLT/") (pintype "bidirectional"))
    )
    (net (code "108") (name "unconnected-(U$4-Pad5V)") (class "Default")
      (node (ref "U$4") (pin "5V") (pinfunction "5V_5V") (pintype "bidirectional"))
    )
    (net (code "109") (name "unconnected-(U$4-PadAREF)") (class "Default")
      (node (ref "U$4") (pin "AREF") (pinfunction "AREF_AREF") (pintype "bidirectional"))
    )
    (net (code "110") (name "unconnected-(U$4-PadGND1)") (class "Default")
      (node (ref "U$4") (pin "GND1") (pinfunction "GND1_GND1") (pintype "bidirectional"))
    )
    (net (code "111") (name "unconnected-(U$4-PadNRST1)") (class "Default")
      (node (ref "U$4") (pin "NRST1") (pinfunction "NRST1_NRST1") (pintype "bidirectional"))
    )
    (net (code "112") (name "unconnected-(U$4-PadNRST2)") (class "Default")
      (node (ref "U$4") (pin "NRST2") (pinfunction "NRST2_NRST2") (pintype "bidirectional"))
    )
    (net (code "113") (name "unconnected-(U$4-PadPA0)") (class "Default")
      (node (ref "U$4") (pin "PA0") (pinfunction "PA0_PA0") (pintype "bidirectional"))
    )
    (net (code "114") (name "unconnected-(U$4-PadPA1)") (class "Default")
      (node (ref "U$4") (pin "PA1") (pinfunction "PA1_PA1") (pintype "bidirectional"))
    )
    (net (code "115") (name "unconnected-(U$4-PadPA3)") (class "Default")
      (node (ref "U$4") (pin "PA3") (pinfunction "PA3_PA3") (pintype "bidirectional"))
    )
    (net (code "116") (name "unconnected-(U$4-PadPA4)") (class "Default")
      (node (ref "U$4") (pin "PA4") (pinfunction "PA4_PA4") (pintype "bidirectional"))
    )
    (net (code "117") (name "unconnected-(U$4-PadPA5)") (class "Default")
      (node (ref "U$4") (pin "PA5") (pinfunction "PA5_PA5") (pintype "bidirectional"))
    )
    (net (code "118") (name "unconnected-(U$4-PadPA6)") (class "Default")
      (node (ref "U$4") (pin "PA6") (pinfunction "PA6_PA6") (pintype "bidirectional"))
    )
    (net (code "119") (name "unconnected-(U$4-PadPA7)") (class "Default")
      (node (ref "U$4") (pin "PA7") (pinfunction "PA7_PA7") (pintype "bidirectional"))
    )
    (net (code "120") (name "unconnected-(U$4-PadPA8)") (class "Default")
      (node (ref "U$4") (pin "PA8") (pinfunction "PA8_PA8") (pintype "bidirectional"))
    )
    (net (code "121") (name "unconnected-(U$4-PadPA12)") (class "Default")
      (node (ref "U$4") (pin "PA12") (pinfunction "PA12_PA12") (pintype "bidirectional"))
    )
    (net (code "122") (name "unconnected-(U$4-PadPB0)") (class "Default")
      (node (ref "U$4") (pin "PB0") (pinfunction "PB0_PB0") (pintype "bidirectional"))
    )
    (net (code "123") (name "unconnected-(U$4-PadPB1)") (class "Default")
      (node (ref "U$4") (pin "PB1") (pinfunction "PB1_PB1") (pintype "bidirectional"))
    )
    (net (code "124") (name "unconnected-(U$4-PadPF0)") (class "Default")
      (node (ref "U$4") (pin "PF0") (pinfunction "PF0_PF0") (pintype "bidirectional"))
    )
    (net (code "125") (name "unconnected-(U$4-PadPF1)") (class "Default")
      (node (ref "U$4") (pin "PF1") (pinfunction "PF1_PF1") (pintype "bidirectional"))
    )
    (net (code "126") (name "unconnected-(U$5-PadD1)") (class "Default")
      (node (ref "U$5") (pin "D1") (pinfunction "D1_D1") (pintype "bidirectional"))
    )
    (net (code "127") (name "unconnected-(U$5-PadD2)") (class "Default")
      (node (ref "U$5") (pin "D2") (pinfunction "D2_D2") (pintype "bidirectional"))
    )
    (net (code "128") (name "unconnected-(U$5-PadD3)") (class "Default")
      (node (ref "U$5") (pin "D3") (pinfunction "D3_D3") (pintype "bidirectional"))
    )
    (net (code "129") (name "unconnected-(U$5-PadD4)") (class "Default")
      (node (ref "U$5") (pin "D4") (pinfunction "D4_D4") (pintype "bidirectional"))
    )
    (net (code "130") (name "unconnected-(U$5-PadD5)") (class "Default")
      (node (ref "U$5") (pin "D5") (pinfunction "D5_D5") (pintype "bidirectional"))
    )
    (net (code "131") (name "unconnected-(U$5-PadD6)") (class "Default")
      (node (ref "U$5") (pin "D6") (pinfunction "D6_D6") (pintype "bidirectional"))
    )
    (net (code "132") (name "unconnected-(U$5-PadD7)") (class "Default")
      (node (ref "U$5") (pin "D7") (pinfunction "D7_D7") (pintype "bidirectional"))
    )
    (net (code "133") (name "unconnected-(U$5-PadD8)") (class "Default")
      (node (ref "U$5") (pin "D8") (pinfunction "D8_D8") (pintype "bidirectional"))
    )
    (net (code "134") (name "unconnected-(U$5-PadD9)") (class "Default")
      (node (ref "U$5") (pin "D9") (pinfunction "D9_D9") (pintype "bidirectional"))
    )
    (net (code "135") (name "unconnected-(U$5-PadD10)") (class "Default")
      (node (ref "U$5") (pin "D10") (pinfunction "D10_D10") (pintype "bidirectional"))
    )
    (net (code "136") (name "unconnected-(U$5-PadD11)") (class "Default")
      (node (ref "U$5") (pin "D11") (pinfunction "D11_D11") (pintype "bidirectional"))
    )
    (net (code "137") (name "unconnected-(U$5-PadD12)") (class "Default")
      (node (ref "U$5") (pin "D12") (pinfunction "D12_D12") (pintype "bidirectional"))
    )
    (net (code "138") (name "unconnected-(U$5-PadG1)") (class "Default")
      (node (ref "U$5") (pin "G1") (pinfunction "G1_G1") (pintype "bidirectional"))
    )
    (net (code "139") (name "unconnected-(U$5-PadG2)") (class "Default")
      (node (ref "U$5") (pin "G2") (pinfunction "G2_G2") (pintype "bidirectional"))
    )
    (net (code "140") (name "unconnected-(U$5-PadG3)") (class "Default")
      (node (ref "U$5") (pin "G3") (pinfunction "G3_G3") (pintype "bidirectional"))
    )
    (net (code "141") (name "unconnected-(U$5-PadG4)") (class "Default")
      (node (ref "U$5") (pin "G4") (pinfunction "G4_G4") (pintype "bidirectional"))
    )
    (net (code "142") (name "unconnected-(U$5-PadG5)") (class "Default")
      (node (ref "U$5") (pin "G5") (pinfunction "G5_G5") (pintype "bidirectional"))
    )
    (net (code "143") (name "unconnected-(U$5-PadG6)") (class "Default")
      (node (ref "U$5") (pin "G6") (pinfunction "G6_G6") (pintype "bidirectional"))
    )
    (net (code "144") (name "unconnected-(U$5-PadG7)") (class "Default")
      (node (ref "U$5") (pin "G7") (pinfunction "G7_G7") (pintype "bidirectional"))
    )
    (net (code "145") (name "unconnected-(U$5-PadG8)") (class "Default")
      (node (ref "U$5") (pin "G8") (pinfunction "G8_G8") (pintype "bidirectional"))
    )
    (net (code "146") (name "unconnected-(U$5-PadG9)") (class "Default")
      (node (ref "U$5") (pin "G9") (pinfunction "G9_G9") (pintype "bidirectional"))
    )
    (net (code "147") (name "unconnected-(U$5-PadG10)") (class "Default")
      (node (ref "U$5") (pin "G10") (pinfunction "G10_G10") (pintype "bidirectional"))
    )
    (net (code "148") (name "unconnected-(U$5-PadG11)") (class "Default")
      (node (ref "U$5") (pin "G11") (pinfunction "G11_G11") (pintype "bidirectional"))
    )
    (net (code "149") (name "unconnected-(U$5-PadG12)") (class "Default")
      (node (ref "U$5") (pin "G12") (pinfunction "G12_G12") (pintype "bidirectional"))
    )
    (net (code "150") (name "unconnected-(U1-NC-Pad8)") (class "Default")
      (node (ref "U1") (pin "8") (pinfunction "NC_8") (pintype "passive"))
    )
    (net (code "151") (name "unconnected-(U1-NC_2-Pad1)") (class "Default")
      (node (ref "U1") (pin "1") (pinfunction "NC_2_1") (pintype "passive"))
    )
    (net (code "152") (name "unconnected-(U1-NC_3-Pad5)") (class "Default")
      (node (ref "U1") (pin "5") (pinfunction "NC_3_5") (pintype "passive"))
    )
  )
)
